# PowerSupply.net
KiCad netlist of a schematic drawn in Altium Designer
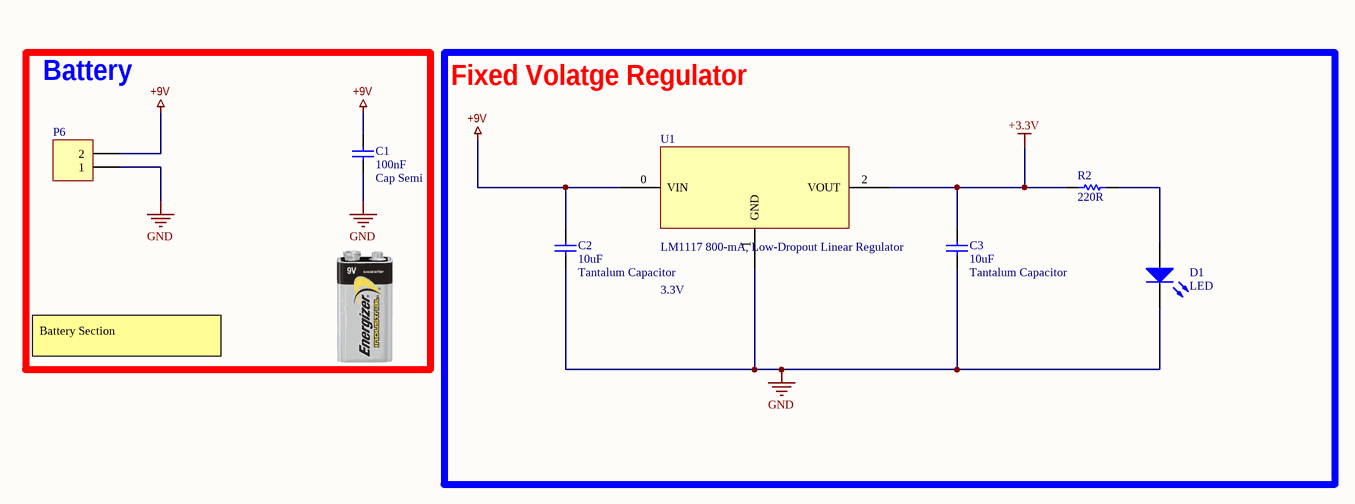
[diagram p0: PowerSupply.SchDoc]

(export (version "E")
  (design (tool "Eeschema 10.0.6"))
  (components
    (comp (ref "C1")
      (value "Cap Semi")
      (footprint "C1206")
      (description "Capacitor (Semiconductor SIM Model)")
      (fields (field (name "ALTIUM_VALUE") "100nF") (field (name "PUBLISHER") "Altium Limited"))
      (libsource (lib "Miscellaneous Devices") (part "Cap Semi"))
    )
    (comp (ref "C2")
      (value "Tantalum Capacitor")
      (footprint "C1206")
      (description "Capacitor (Semiconductor SIM Model)")
      (fields (field (name "ALTIUM_VALUE") "10uF") (field (name "PUBLISHER") "Altium Limited"))
      (libsource (lib "Miscellaneous Devices") (part "Cap Semi"))
    )
    (comp (ref "C3")
      (value "Tantalum Capacitor")
      (footprint "C1206")
      (description "Capacitor (Semiconductor SIM Model)")
      (fields (field (name "ALTIUM_VALUE") "10uF") (field (name "PUBLISHER") "Altium Limited"))
      (libsource (lib "Miscellaneous Devices") (part "Cap Semi"))
    )
    (comp (ref "D1")
      (value "LED")
      (footprint "MY_LED_0805")
      (description "Typical INFRARED GaAs LED")
      (fields (field (name "ASID PART NUMBER") "LED-AS"))
      (libsource (lib "Mylib+Rev+4") (part "LED"))
    )
    (comp (ref "P6")
      (value "Header 2")
      (footprint "My_1X02")
      (description "Header, 2-Pin")
      (fields (field (name "ASID PART NUMBER") "Header 2-AS"))
      (libsource (lib "Mylib+Rev+4") (part "Header 2"))
    )
    (comp (ref "R2")
      (value "220R")
      (footprint "MY_0805")
      (description "Standard resistor")
      (fields (field (name "ASID PART NUMBER") "Res-AS"))
      (libsource (lib "Mylib+Rev+4") (part "Res"))
    )
    (comp (ref "U1")
      (value "LM1117 800-mA, Low-Dropout Linear Regulator")
      (footprint "4-pin SOT")
      (fields (field (name "MANUFACTURER") "Texas Instruments (TI)") (field (name "VOLTAGE") "3.3V"))
      (libsource (lib "First-PCB-Project") (part "lm1117"))
    )
  )
  (nets
    (net (code "1") (name "+3.3V") (class "Default")
      (node (ref "C3") (pin "2") (pinfunction "2_2") (pintype "passive"))
      (node (ref "R2") (pin "1") (pinfunction "1_1") (pintype "passive"))
      (node (ref "U1") (pin "2") (pinfunction "VOUT_2") (pintype "passive"))
    )
    (net (code "2") (name "+9V") (class "Default")
      (node (ref "C1") (pin "2") (pinfunction "2_2") (pintype "passive"))
      (node (ref "C2") (pin "2") (pinfunction "2_2") (pintype "passive"))
      (node (ref "P6") (pin "2") (pinfunction "2_2") (pintype "passive"))
      (node (ref "U1") (pin "0") (pinfunction "VIN_0") (pintype "passive"))
    )
    (net (code "3") (name "GND") (class "Default")
      (node (ref "C1") (pin "1") (pinfunction "1_1") (pintype "passive"))
      (node (ref "C2") (pin "1") (pinfunction "1_1") (pintype "passive"))
      (node (ref "C3") (pin "1") (pinfunction "1_1") (pintype "passive"))
      (node (ref "D1") (pin "K") (pinfunction "K_K") (pintype "passive"))
      (node (ref "P6") (pin "1") (pinfunction "1_1") (pintype "passive"))
      (node (ref "U1") (pin "1") (pinfunction "GND_1") (pintype "passive"))
    )
    (net (code "4") (name "Net-(D1-PadA)") (class "Default")
      (node (ref "D1") (pin "A") (pinfunction "A_A") (pintype "passive"))
      (node (ref "R2") (pin "2") (pinfunction "2_2") (pintype "passive"))
    )
  )
)
